# CurrentSenseAmp.net
KiCad netlist of a schematic drawn in Altium Designer
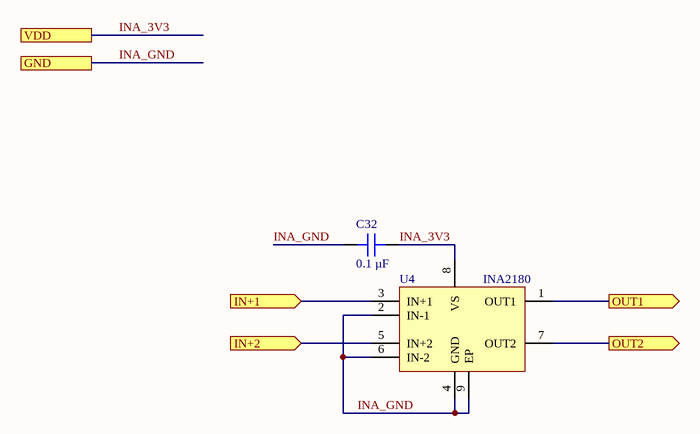
[diagram p0: CurrentSenseAmp.SchDoc]

(export (version "E")
  (design (tool "Eeschema 10.0.6"))
  (components
    (comp (ref "C32")
      (value "0.1 µF")
      (footprint "CAP 0402_1005")
      (description "CAP CER 0.1UF 16V X7R 0402")
      (fields (field (name "PART NUMBER") "C0402C104K4RACAUTO") (field (name "MANUFACTURER") "KEMET"))
      (libsource (lib "Celestial Altium Library - altium_library") (part "Capacitor"))
    )
    (comp (ref "U4")
      (value "INA2180")
      (footprint "WSON-8_2x2")
      (description "Current sense amplifier 4 channel")
      (libsource (lib "IC") (part "INA2180"))
    )
  )
  (nets
    (net (code "1") (name "/IN+1") (class "Default")
      (node (ref "U4") (pin "3") (pinfunction "IN+1_3") (pintype "passive"))
    )
    (net (code "2") (name "/IN+2") (class "Default")
      (node (ref "U4") (pin "5") (pinfunction "IN+2_5") (pintype "passive"))
    )
    (net (code "3") (name "/INA_3V3") (class "Default")
      (node (ref "C32") (pin "1") (pinfunction "1_1") (pintype "passive"))
      (node (ref "U4") (pin "8") (pinfunction "VS_8") (pintype "passive"))
    )
    (net (code "4") (name "/INA_GND") (class "Default")
      (node (ref "C32") (pin "2") (pinfunction "2_2") (pintype "passive"))
      (node (ref "U4") (pin "2") (pinfunction "IN-1_2") (pintype "passive"))
      (node (ref "U4") (pin "4") (pinfunction "GND_4") (pintype "passive"))
      (node (ref "U4") (pin "6") (pinfunction "IN-2_6") (pintype "passive"))
      (node (ref "U4") (pin "9") (pinfunction "EP_9") (pintype "passive"))
    )
    (net (code "5") (name "/OUT1") (class "Default")
      (node (ref "U4") (pin "1") (pinfunction "OUT1_1") (pintype "passive"))
    )
    (net (code "6") (name "/OUT2") (class "Default")
      (node (ref "U4") (pin "7") (pinfunction "OUT2_7") (pintype "passive"))
    )
  )
)
